# PulseFit.net
KiCad netlist of a schematic drawn in EAGLE
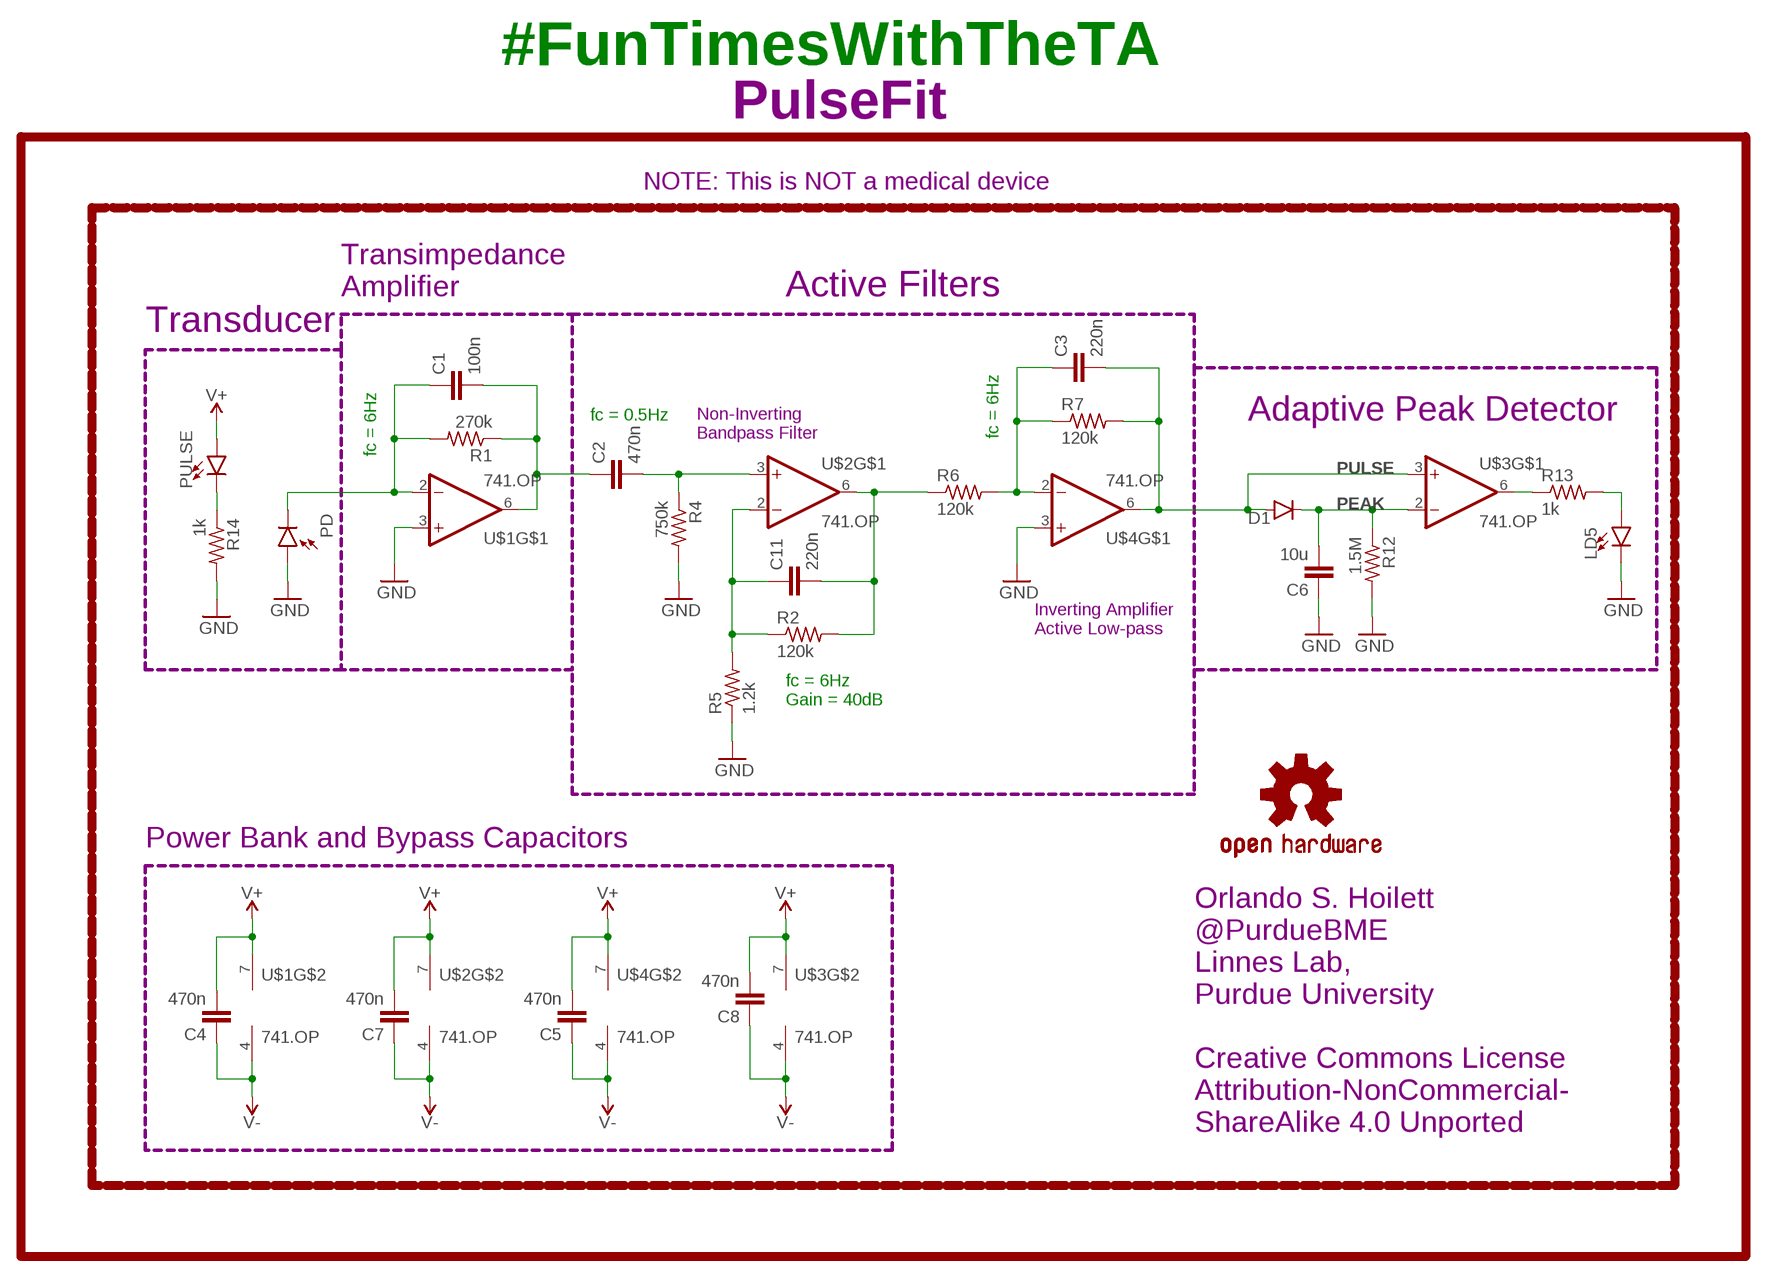
[diagram p0: schematic, sheet 1]

(export (version "E")
  (design (tool "Eeschema 10.0.6"))
  (components
    (comp (ref "C1")
      (value "100n")
      (footprint "eagle-import:C0402")
      (libsource (lib "eagle-import") (part "C-EUC0402"))
    )
    (comp (ref "C2")
      (value "470n")
      (footprint "eagle-import:C0402")
      (libsource (lib "eagle-import") (part "C-EUC0402"))
    )
    (comp (ref "C3")
      (value "220n")
      (footprint "eagle-import:C0402")
      (libsource (lib "eagle-import") (part "C-EUC0402"))
    )
    (comp (ref "C4")
      (value "470n")
      (footprint "eagle-import:C0402")
      (libsource (lib "eagle-import") (part "C-EUC0402"))
    )
    (comp (ref "C5")
      (value "470n")
      (footprint "eagle-import:C0402")
      (libsource (lib "eagle-import") (part "C-EUC0402"))
    )
    (comp (ref "C6")
      (value "10u")
      (footprint "eagle-import:C0805")
      (libsource (lib "eagle-import") (part "C-EUC0805"))
    )
    (comp (ref "C7")
      (value "470n")
      (footprint "eagle-import:C0402")
      (libsource (lib "eagle-import") (part "C-EUC0402"))
    )
    (comp (ref "C8")
      (value "470n")
      (footprint "eagle-import:C0402")
      (libsource (lib "eagle-import") (part "C-EUC0402"))
    )
    (comp (ref "C11")
      (value "220n")
      (footprint "eagle-import:C0402")
      (libsource (lib "eagle-import") (part "C-EUC0402"))
    )
    (comp (ref "D1")
      (value "250mA/100V")
      (footprint "eagle-import:SOD-323")
      (libsource (lib "eagle-import") (part "DIODEBAS16"))
    )
    (comp (ref "LD5")
      (value "LED5MM")
      (footprint "eagle-import:LED_5MM")
      (libsource (lib "eagle-import") (part "LED5MM"))
    )
    (comp (ref "LOGO1")
      (value "OSHW-LOGOS")
      (footprint "eagle-import:OSHW-LOGO-S")
      (libsource (lib "eagle-import") (part "OSHW-LOGOS"))
    )
    (comp (ref "PD")
      (value "PHOTODIODE-5MM")
      (footprint "eagle-import:PD_5MM")
      (libsource (lib "eagle-import") (part "PHOTODIODE-5MM"))
    )
    (comp (ref "PULSE")
      (value "LED5MM")
      (footprint "eagle-import:LED_5MM")
      (libsource (lib "eagle-import") (part "LED5MM"))
    )
    (comp (ref "R1")
      (value "270k")
      (footprint "eagle-import:R0402")
      (libsource (lib "eagle-import") (part "R-US_R0402"))
    )
    (comp (ref "R2")
      (value "120k")
      (footprint "eagle-import:R0402")
      (libsource (lib "eagle-import") (part "R-US_R0402"))
    )
    (comp (ref "R4")
      (value "750k")
      (footprint "eagle-import:R0402")
      (libsource (lib "eagle-import") (part "R-US_R0402"))
    )
    (comp (ref "R5")
      (value "1.2k")
      (footprint "eagle-import:R0402")
      (libsource (lib "eagle-import") (part "R-US_R0402"))
    )
    (comp (ref "R6")
      (value "120k")
      (footprint "eagle-import:R0402")
      (libsource (lib "eagle-import") (part "R-US_R0402"))
    )
    (comp (ref "R7")
      (value "120k")
      (footprint "eagle-import:R0402")
      (libsource (lib "eagle-import") (part "R-US_R0402"))
    )
    (comp (ref "R12")
      (value "1.5M")
      (footprint "eagle-import:R0402")
      (libsource (lib "eagle-import") (part "R-US_R0402"))
    )
    (comp (ref "R13")
      (value "1k")
      (footprint "eagle-import:R0402")
      (libsource (lib "eagle-import") (part "R-US_R0402"))
    )
    (comp (ref "R14")
      (value "1k")
      (footprint "eagle-import:R0402")
      (libsource (lib "eagle-import") (part "R-US_R0402"))
    )
    (comp (ref "U$1")
      (value "741.OP")
      (footprint "eagle-import:DIL08")
      (libsource (lib "eagle-import") (part "741.OP"))
    )
    (comp (ref "U$2")
      (value "741.OP")
      (footprint "eagle-import:DIL08")
      (libsource (lib "eagle-import") (part "741.OP"))
    )
    (comp (ref "U$3")
      (value "741.OP")
      (footprint "eagle-import:DIL08")
      (libsource (lib "eagle-import") (part "741.OP"))
    )
    (comp (ref "U$4")
      (value "741.OP")
      (footprint "eagle-import:DIL08")
      (libsource (lib "eagle-import") (part "741.OP"))
    )
  )
  (nets
    (net (code "1") (name "/PEAK") (class "Default")
      (node (ref "C6") (pin "2") (pinfunction "2_2") (pintype "passive"))
      (node (ref "D1") (pin "C") (pinfunction "C_C") (pintype "passive"))
      (node (ref "R12") (pin "1") (pinfunction "1_1") (pintype "passive"))
      (node (ref "U$3") (pin "2") (pinfunction "-IN_2") (pintype "input"))
    )
    (net (code "2") (name "/PULSE") (class "Default")
      (node (ref "C11") (pin "2") (pinfunction "2_2") (pintype "passive"))
      (node (ref "C3") (pin "2") (pinfunction "2_2") (pintype "passive"))
      (node (ref "D1") (pin "A") (pinfunction "A_A") (pintype "passive"))
      (node (ref "R2") (pin "2") (pinfunction "2_2") (pintype "passive"))
      (node (ref "R6") (pin "1") (pinfunction "1_1") (pintype "passive"))
      (node (ref "R7") (pin "2") (pinfunction "2_2") (pintype "passive"))
      (node (ref "U$2") (pin "6") (pinfunction "OUT_6") (pintype "output"))
      (node (ref "U$3") (pin "3") (pinfunction "+IN_3") (pintype "input"))
      (node (ref "U$4") (pin "6") (pinfunction "OUT_6") (pintype "output"))
    )
    (net (code "3") (name "GND") (class "Default")
      (node (ref "C6") (pin "1") (pinfunction "1_1") (pintype "passive"))
      (node (ref "LD5") (pin "K") (pinfunction "C_K") (pintype "passive"))
      (node (ref "PD") (pin "A") (pinfunction "A_A") (pintype "passive"))
      (node (ref "R12") (pin "2") (pinfunction "2_2") (pintype "passive"))
      (node (ref "R14") (pin "2") (pinfunction "2_2") (pintype "passive"))
      (node (ref "R4") (pin "2") (pinfunction "2_2") (pintype "passive"))
      (node (ref "R5") (pin "1") (pinfunction "1_1") (pintype "passive"))
      (node (ref "U$1") (pin "3") (pinfunction "+IN_3") (pintype "input"))
      (node (ref "U$4") (pin "3") (pinfunction "+IN_3") (pintype "input"))
    )
    (net (code "4") (name "Net-(LD5-PadA)") (class "Default")
      (node (ref "LD5") (pin "A") (pinfunction "A_A") (pintype "passive"))
      (node (ref "R13") (pin "2") (pinfunction "2_2") (pintype "passive"))
    )
    (net (code "5") (name "Net-(PD-C)") (class "Default")
      (node (ref "C1") (pin "1") (pinfunction "1_1") (pintype "passive"))
      (node (ref "PD") (pin "K") (pinfunction "C_K") (pintype "passive"))
      (node (ref "R1") (pin "2") (pinfunction "2_2") (pintype "passive"))
      (node (ref "U$1") (pin "2") (pinfunction "-IN_2") (pintype "input"))
    )
    (net (code "6") (name "Net-(PULSE-C)") (class "Default")
      (node (ref "PULSE") (pin "K") (pinfunction "C_K") (pintype "passive"))
      (node (ref "R14") (pin "1") (pinfunction "1_1") (pintype "passive"))
    )
    (net (code "7") (name "Net-(U$1A-OUT)") (class "Default")
      (node (ref "C1") (pin "2") (pinfunction "2_2") (pintype "passive"))
      (node (ref "C2") (pin "1") (pinfunction "1_1") (pintype "passive"))
      (node (ref "R1") (pin "1") (pinfunction "1_1") (pintype "passive"))
      (node (ref "U$1") (pin "6") (pinfunction "OUT_6") (pintype "output"))
    )
    (net (code "8") (name "Net-(U$2A-+IN)") (class "Default")
      (node (ref "C2") (pin "2") (pinfunction "2_2") (pintype "passive"))
      (node (ref "R4") (pin "1") (pinfunction "1_1") (pintype "passive"))
      (node (ref "U$2") (pin "3") (pinfunction "+IN_3") (pintype "input"))
    )
    (net (code "9") (name "Net-(U$2A--IN)") (class "Default")
      (node (ref "C11") (pin "1") (pinfunction "1_1") (pintype "passive"))
      (node (ref "R2") (pin "1") (pinfunction "1_1") (pintype "passive"))
      (node (ref "R5") (pin "2") (pinfunction "2_2") (pintype "passive"))
      (node (ref "U$2") (pin "2") (pinfunction "-IN_2") (pintype "input"))
    )
    (net (code "10") (name "Net-(U$3A-OUT)") (class "Default")
      (node (ref "R13") (pin "1") (pinfunction "1_1") (pintype "passive"))
      (node (ref "U$3") (pin "6") (pinfunction "OUT_6") (pintype "output"))
    )
    (net (code "11") (name "Net-(U$4A--IN)") (class "Default")
      (node (ref "C3") (pin "1") (pinfunction "1_1") (pintype "passive"))
      (node (ref "R6") (pin "2") (pinfunction "2_2") (pintype "passive"))
      (node (ref "R7") (pin "1") (pinfunction "1_1") (pintype "passive"))
      (node (ref "U$4") (pin "2") (pinfunction "-IN_2") (pintype "input"))
    )
    (net (code "12") (name "V+") (class "Default")
      (node (ref "C4") (pin "2") (pinfunction "2_2") (pintype "passive"))
      (node (ref "C5") (pin "2") (pinfunction "2_2") (pintype "passive"))
      (node (ref "C7") (pin "2") (pinfunction "2_2") (pintype "passive"))
      (node (ref "C8") (pin "2") (pinfunction "2_2") (pintype "passive"))
      (node (ref "PULSE") (pin "A") (pinfunction "A_A") (pintype "passive"))
      (node (ref "U$1") (pin "7") (pinfunction "V+_7") (pintype "power_in"))
      (node (ref "U$2") (pin "7") (pinfunction "V+_7") (pintype "power_in"))
      (node (ref "U$3") (pin "7") (pinfunction "V+_7") (pintype "power_in"))
      (node (ref "U$4") (pin "7") (pinfunction "V+_7") (pintype "power_in"))
    )
    (net (code "13") (name "V-") (class "Default")
      (node (ref "C4") (pin "1") (pinfunction "1_1") (pintype "passive"))
      (node (ref "C5") (pin "1") (pinfunction "1_1") (pintype "passive"))
      (node (ref "C7") (pin "1") (pinfunction "1_1") (pintype "passive"))
      (node (ref "C8") (pin "1") (pinfunction "1_1") (pintype "passive"))
      (node (ref "U$1") (pin "4") (pinfunction "V-_4") (pintype "power_in"))
      (node (ref "U$2") (pin "4") (pinfunction "V-_4") (pintype "power_in"))
      (node (ref "U$3") (pin "4") (pinfunction "V-_4") (pintype "power_in"))
      (node (ref "U$4") (pin "4") (pinfunction "V-_4") (pintype "power_in"))
    )
  )
)
